# motorController.net
KiCad netlist of a schematic drawn in Altium Designer
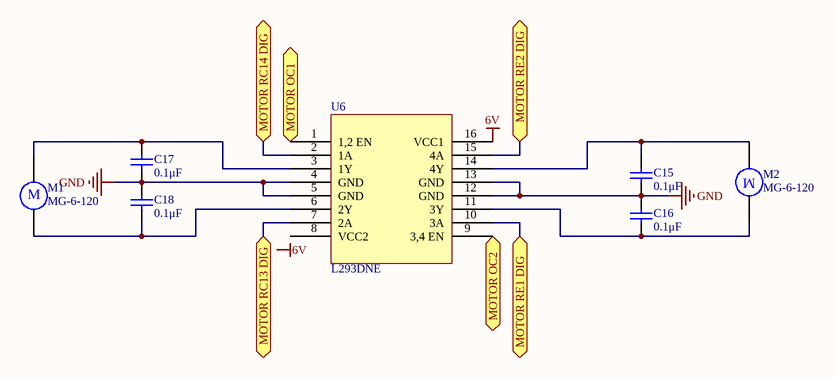
[diagram p0: motorController.SchDoc]

(export (version "E")
  (design (tool "Eeschema 10.0.6"))
  (components
    (comp (ref "C15")
      (value "0.1μF")
      (footprint "capacitor")
      (description "Capacitor")
      (fields (field (name "PUBLISHER") "Altium Limited"))
      (libsource (lib "Miscellaneous Devices") (part "Cap"))
    )
    (comp (ref "C16")
      (value "0.1μF")
      (footprint "capacitor")
      (description "Capacitor")
      (fields (field (name "PUBLISHER") "Altium Limited"))
      (libsource (lib "Miscellaneous Devices") (part "Cap"))
    )
    (comp (ref "C17")
      (value "0.1μF")
      (footprint "capacitor")
      (description "Capacitor")
      (fields (field (name "PUBLISHER") "Altium Limited"))
      (libsource (lib "Miscellaneous Devices") (part "Cap"))
    )
    (comp (ref "C18")
      (value "0.1μF")
      (footprint "capacitor")
      (description "Capacitor")
      (fields (field (name "PUBLISHER") "Altium Limited"))
      (libsource (lib "Miscellaneous Devices") (part "Cap"))
    )
    (comp (ref "M1")
      (value "MG-6-120")
      (footprint "Motor2")
      (description "Motor, General Kind")
      (fields (field (name "PUBLISHER") "Altium Limited"))
      (libsource (lib "Miscellaneous Devices") (part "Motor"))
    )
    (comp (ref "M2")
      (value "MG-6-120")
      (footprint "Motor2")
      (description "Motor, General Kind")
      (fields (field (name "PUBLISHER") "Altium Limited"))
      (libsource (lib "Miscellaneous Devices") (part "Motor"))
    )
    (comp (ref "U6")
      (value "L293DNE")
      (footprint "MotorDriver")
      (libsource (lib "PROBOT_Schema_Library") (part "Motor Driver"))
    )
  )
  (nets
    (net (code "1") (name "/MOTOR OC1") (class "Default")
      (node (ref "U6") (pin "1") (pinfunction "1,2_EN_1") (pintype "passive"))
    )
    (net (code "2") (name "/MOTOR OC2") (class "Default")
      (node (ref "U6") (pin "9") (pinfunction "3,4_EN_9") (pintype "passive"))
    )
    (net (code "3") (name "/MOTOR RC13 DIG") (class "Default")
      (node (ref "U6") (pin "7") (pinfunction "2A_7") (pintype "passive"))
    )
    (net (code "4") (name "/MOTOR RC14 DIG") (class "Default")
      (node (ref "U6") (pin "2") (pinfunction "1A_2") (pintype "passive"))
    )
    (net (code "5") (name "/MOTOR RE1 DIG") (class "Default")
      (node (ref "U6") (pin "10") (pinfunction "3A_10") (pintype "passive"))
    )
    (net (code "6") (name "/MOTOR RE2 DIG") (class "Default")
      (node (ref "U6") (pin "15") (pinfunction "4A_15") (pintype "passive"))
    )
    (net (code "7") (name "6V") (class "Default")
      (node (ref "U6") (pin "16") (pinfunction "VCC1_16") (pintype "passive"))
    )
    (net (code "8") (name "GND") (class "Default")
      (node (ref "C15") (pin "2") (pinfunction "2_2") (pintype "passive"))
      (node (ref "C16") (pin "1") (pinfunction "1_1") (pintype "passive"))
      (node (ref "C17") (pin "1") (pinfunction "1_1") (pintype "passive"))
      (node (ref "C18") (pin "2") (pinfunction "2_2") (pintype "passive"))
      (node (ref "U6") (pin "12") (pinfunction "GND_12") (pintype "passive"))
      (node (ref "U6") (pin "13") (pinfunction "GND_13") (pintype "passive"))
      (node (ref "U6") (pin "4") (pinfunction "GND_4") (pintype "passive"))
      (node (ref "U6") (pin "5") (pinfunction "GND_5") (pintype "passive"))
    )
    (net (code "9") (name "Net-(U6-1Y)") (class "Default")
      (node (ref "C17") (pin "2") (pinfunction "2_2") (pintype "passive"))
      (node (ref "M1") (pin "1") (pinfunction "1_1") (pintype "passive"))
      (node (ref "U6") (pin "3") (pinfunction "1Y_3") (pintype "passive"))
    )
    (net (code "10") (name "Net-(U6-2Y)") (class "Default")
      (node (ref "C18") (pin "1") (pinfunction "1_1") (pintype "passive"))
      (node (ref "M1") (pin "2") (pinfunction "2_2") (pintype "passive"))
      (node (ref "U6") (pin "6") (pinfunction "2Y_6") (pintype "passive"))
    )
    (net (code "11") (name "Net-(U6-3Y)") (class "Default")
      (node (ref "C16") (pin "2") (pinfunction "2_2") (pintype "passive"))
      (node (ref "M2") (pin "1") (pinfunction "1_1") (pintype "passive"))
      (node (ref "U6") (pin "11") (pinfunction "3Y_11") (pintype "passive"))
    )
    (net (code "12") (name "Net-(U6-4Y)") (class "Default")
      (node (ref "C15") (pin "1") (pinfunction "1_1") (pintype "passive"))
      (node (ref "M2") (pin "2") (pinfunction "2_2") (pintype "passive"))
      (node (ref "U6") (pin "14") (pinfunction "4Y_14") (pintype "passive"))
    )
    (net (code "13") (name "unconnected-(U6-VCC2-Pad8)") (class "Default")
      (node (ref "U6") (pin "8") (pinfunction "VCC2_8") (pintype "passive"))
    )
  )
)
